# Callisto_LSOx10_v1p1.net
KiCad netlist of a schematic drawn in EAGLE
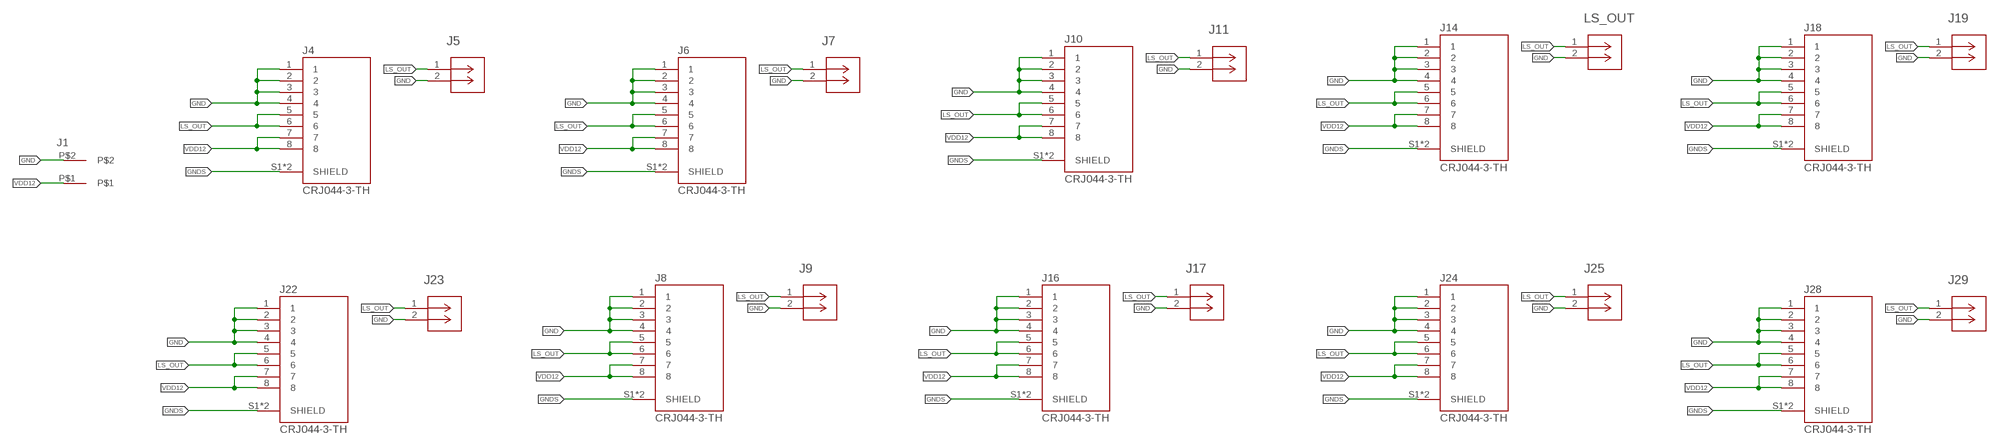
[diagram p0: schematic, sheet 1]

(export (version "E")
  (design (tool "Eeschema 10.0.6"))
  (components
    (comp (ref "J1")
      (value "2-pos")
      (footprint "eagle-import:2_3.81MM_PITCH")
      (fields (field (name "PARTNO") "691322310002"))
      (libsource (lib "eagle-import") (part "3.81MM_1_X_2_RT_ANGLE_PLUG_HEADER"))
    )
    (comp (ref "J4")
      (value "CRJ044-3-TH")
      (footprint "eagle-import:CUI_CRJ044-3-TH")
      (libsource (lib "eagle-import") (part "CRJ044-3-TH"))
    )
    (comp (ref "J5")
      (value "CONN_530470210_PICOBLADE_X_2")
      (footprint "eagle-import:CON_530470210_MOL")
      (fields
        (field (name "MANUFACTURER_PART_NUMBER") "530470210")
        (field (name "COPYRIGHT") "Copyright (C) 2022 Ultra Librarian. All rights reserved.")
      )
      (libsource (lib "eagle-import") (part "CONN_530470210_PICOBLADE_X_2"))
    )
    (comp (ref "J6")
      (value "CRJ044-3-TH")
      (footprint "eagle-import:CUI_CRJ044-3-TH")
      (libsource (lib "eagle-import") (part "CRJ044-3-TH"))
    )
    (comp (ref "J7")
      (value "CONN_530470210_PICOBLADE_X_2")
      (footprint "eagle-import:CON_530470210_MOL")
      (fields
        (field (name "MANUFACTURER_PART_NUMBER") "530470210")
        (field (name "COPYRIGHT") "Copyright (C) 2022 Ultra Librarian. All rights reserved.")
      )
      (libsource (lib "eagle-import") (part "CONN_530470210_PICOBLADE_X_2"))
    )
    (comp (ref "J8")
      (value "CRJ044-3-TH")
      (footprint "eagle-import:CUI_CRJ044-3-TH")
      (libsource (lib "eagle-import") (part "CRJ044-3-TH"))
    )
    (comp (ref "J9")
      (value "CONN_530470210_PICOBLADE_X_2")
      (footprint "eagle-import:CON_530470210_MOL")
      (fields
        (field (name "MANUFACTURER_PART_NUMBER") "530470210")
        (field (name "COPYRIGHT") "Copyright (C) 2022 Ultra Librarian. All rights reserved.")
      )
      (libsource (lib "eagle-import") (part "CONN_530470210_PICOBLADE_X_2"))
    )
    (comp (ref "J10")
      (value "CRJ044-3-TH")
      (footprint "eagle-import:CUI_CRJ044-3-TH")
      (libsource (lib "eagle-import") (part "CRJ044-3-TH"))
    )
    (comp (ref "J11")
      (value "CONN_530470210_PICOBLADE_X_2")
      (footprint "eagle-import:CON_530470210_MOL")
      (fields
        (field (name "MANUFACTURER_PART_NUMBER") "530470210")
        (field (name "COPYRIGHT") "Copyright (C) 2022 Ultra Librarian. All rights reserved.")
      )
      (libsource (lib "eagle-import") (part "CONN_530470210_PICOBLADE_X_2"))
    )
    (comp (ref "J14")
      (value "CRJ044-3-TH")
      (footprint "eagle-import:CUI_CRJ044-3-TH")
      (libsource (lib "eagle-import") (part "CRJ044-3-TH"))
    )
    (comp (ref "J16")
      (value "CRJ044-3-TH")
      (footprint "eagle-import:CUI_CRJ044-3-TH")
      (libsource (lib "eagle-import") (part "CRJ044-3-TH"))
    )
    (comp (ref "J17")
      (value "CONN_530470210_PICOBLADE_X_2")
      (footprint "eagle-import:CON_530470210_MOL")
      (fields
        (field (name "MANUFACTURER_PART_NUMBER") "530470210")
        (field (name "COPYRIGHT") "Copyright (C) 2022 Ultra Librarian. All rights reserved.")
      )
      (libsource (lib "eagle-import") (part "CONN_530470210_PICOBLADE_X_2"))
    )
    (comp (ref "J18")
      (value "CRJ044-3-TH")
      (footprint "eagle-import:CUI_CRJ044-3-TH")
      (libsource (lib "eagle-import") (part "CRJ044-3-TH"))
    )
    (comp (ref "J19")
      (value "CONN_530470210_PICOBLADE_X_2")
      (footprint "eagle-import:CON_530470210_MOL")
      (fields
        (field (name "MANUFACTURER_PART_NUMBER") "530470210")
        (field (name "COPYRIGHT") "Copyright (C) 2022 Ultra Librarian. All rights reserved.")
      )
      (libsource (lib "eagle-import") (part "CONN_530470210_PICOBLADE_X_2"))
    )
    (comp (ref "J22")
      (value "CRJ044-3-TH")
      (footprint "eagle-import:CUI_CRJ044-3-TH")
      (libsource (lib "eagle-import") (part "CRJ044-3-TH"))
    )
    (comp (ref "J23")
      (value "CONN_530470210_PICOBLADE_X_2")
      (footprint "eagle-import:CON_530470210_MOL")
      (fields
        (field (name "MANUFACTURER_PART_NUMBER") "530470210")
        (field (name "COPYRIGHT") "Copyright (C) 2022 Ultra Librarian. All rights reserved.")
      )
      (libsource (lib "eagle-import") (part "CONN_530470210_PICOBLADE_X_2"))
    )
    (comp (ref "J24")
      (value "CRJ044-3-TH")
      (footprint "eagle-import:CUI_CRJ044-3-TH")
      (libsource (lib "eagle-import") (part "CRJ044-3-TH"))
    )
    (comp (ref "J25")
      (value "CONN_530470210_PICOBLADE_X_2")
      (footprint "eagle-import:CON_530470210_MOL")
      (fields
        (field (name "MANUFACTURER_PART_NUMBER") "530470210")
        (field (name "COPYRIGHT") "Copyright (C) 2022 Ultra Librarian. All rights reserved.")
      )
      (libsource (lib "eagle-import") (part "CONN_530470210_PICOBLADE_X_2"))
    )
    (comp (ref "J28")
      (value "CRJ044-3-TH")
      (footprint "eagle-import:CUI_CRJ044-3-TH")
      (libsource (lib "eagle-import") (part "CRJ044-3-TH"))
    )
    (comp (ref "J29")
      (value "CONN_530470210_PICOBLADE_X_2")
      (footprint "eagle-import:CON_530470210_MOL")
      (fields
        (field (name "MANUFACTURER_PART_NUMBER") "530470210")
        (field (name "COPYRIGHT") "Copyright (C) 2022 Ultra Librarian. All rights reserved.")
      )
      (libsource (lib "eagle-import") (part "CONN_530470210_PICOBLADE_X_2"))
    )
    (comp (ref "LS_OUT")
      (value "CONN_530470210_PICOBLADE_X_2")
      (footprint "eagle-import:CON_530470210_MOL")
      (fields
        (field (name "MANUFACTURER_PART_NUMBER") "530470210")
        (field (name "COPYRIGHT") "Copyright (C) 2022 Ultra Librarian. All rights reserved.")
      )
      (libsource (lib "eagle-import") (part "CONN_530470210_PICOBLADE_X_2"))
    )
  )
  (nets
    (net (code "1") (name "GND") (class "Default")
      (node (ref "J1") (pin "P$2") (pinfunction "P$2_P$2") (pintype "bidirectional"))
      (node (ref "J10") (pin "1") (pinfunction "1_1") (pintype "passive"))
      (node (ref "J10") (pin "2") (pinfunction "2_2") (pintype "passive"))
      (node (ref "J10") (pin "3") (pinfunction "3_3") (pintype "passive"))
      (node (ref "J10") (pin "4") (pinfunction "4_4") (pintype "passive"))
      (node (ref "J11") (pin "2") (pinfunction "2_2") (pintype "passive"))
      (node (ref "J14") (pin "1") (pinfunction "1_1") (pintype "passive"))
      (node (ref "J14") (pin "2") (pinfunction "2_2") (pintype "passive"))
      (node (ref "J14") (pin "3") (pinfunction "3_3") (pintype "passive"))
      (node (ref "J14") (pin "4") (pinfunction "4_4") (pintype "passive"))
      (node (ref "J16") (pin "1") (pinfunction "1_1") (pintype "passive"))
      (node (ref "J16") (pin "2") (pinfunction "2_2") (pintype "passive"))
      (node (ref "J16") (pin "3") (pinfunction "3_3") (pintype "passive"))
      (node (ref "J16") (pin "4") (pinfunction "4_4") (pintype "passive"))
      (node (ref "J17") (pin "2") (pinfunction "2_2") (pintype "passive"))
      (node (ref "J18") (pin "1") (pinfunction "1_1") (pintype "passive"))
      (node (ref "J18") (pin "2") (pinfunction "2_2") (pintype "passive"))
      (node (ref "J18") (pin "3") (pinfunction "3_3") (pintype "passive"))
      (node (ref "J18") (pin "4") (pinfunction "4_4") (pintype "passive"))
      (node (ref "J19") (pin "2") (pinfunction "2_2") (pintype "passive"))
      (node (ref "J22") (pin "1") (pinfunction "1_1") (pintype "passive"))
      (node (ref "J22") (pin "2") (pinfunction "2_2") (pintype "passive"))
      (node (ref "J22") (pin "3") (pinfunction "3_3") (pintype "passive"))
      (node (ref "J22") (pin "4") (pinfunction "4_4") (pintype "passive"))
      (node (ref "J23") (pin "2") (pinfunction "2_2") (pintype "passive"))
      (node (ref "J24") (pin "1") (pinfunction "1_1") (pintype "passive"))
      (node (ref "J24") (pin "2") (pinfunction "2_2") (pintype "passive"))
      (node (ref "J24") (pin "3") (pinfunction "3_3") (pintype "passive"))
      (node (ref "J24") (pin "4") (pinfunction "4_4") (pintype "passive"))
      (node (ref "J25") (pin "2") (pinfunction "2_2") (pintype "passive"))
      (node (ref "J28") (pin "1") (pinfunction "1_1") (pintype "passive"))
      (node (ref "J28") (pin "2") (pinfunction "2_2") (pintype "passive"))
      (node (ref "J28") (pin "3") (pinfunction "3_3") (pintype "passive"))
      (node (ref "J28") (pin "4") (pinfunction "4_4") (pintype "passive"))
      (node (ref "J29") (pin "2") (pinfunction "2_2") (pintype "passive"))
      (node (ref "J4") (pin "1") (pinfunction "1_1") (pintype "passive"))
      (node (ref "J4") (pin "2") (pinfunction "2_2") (pintype "passive"))
      (node (ref "J4") (pin "3") (pinfunction "3_3") (pintype "passive"))
      (node (ref "J4") (pin "4") (pinfunction "4_4") (pintype "passive"))
      (node (ref "J5") (pin "2") (pinfunction "2_2") (pintype "passive"))
      (node (ref "J6") (pin "1") (pinfunction "1_1") (pintype "passive"))
      (node (ref "J6") (pin "2") (pinfunction "2_2") (pintype "passive"))
      (node (ref "J6") (pin "3") (pinfunction "3_3") (pintype "passive"))
      (node (ref "J6") (pin "4") (pinfunction "4_4") (pintype "passive"))
      (node (ref "J7") (pin "2") (pinfunction "2_2") (pintype "passive"))
      (node (ref "J8") (pin "1") (pinfunction "1_1") (pintype "passive"))
      (node (ref "J8") (pin "2") (pinfunction "2_2") (pintype "passive"))
      (node (ref "J8") (pin "3") (pinfunction "3_3") (pintype "passive"))
      (node (ref "J8") (pin "4") (pinfunction "4_4") (pintype "passive"))
      (node (ref "J9") (pin "2") (pinfunction "2_2") (pintype "passive"))
      (node (ref "LS_OUT") (pin "2") (pinfunction "2_2") (pintype "passive"))
    )
    (net (code "2") (name "GNDS") (class "Default")
      (node (ref "J10") (pin "S1") (pinfunction "SHIELD_S1") (pintype "passive"))
      (node (ref "J10") (pin "S2") (pinfunction "SHIELD_S2") (pintype "passive"))
      (node (ref "J14") (pin "S1") (pinfunction "SHIELD_S1") (pintype "passive"))
      (node (ref "J14") (pin "S2") (pinfunction "SHIELD_S2") (pintype "passive"))
      (node (ref "J16") (pin "S1") (pinfunction "SHIELD_S1") (pintype "passive"))
      (node (ref "J16") (pin "S2") (pinfunction "SHIELD_S2") (pintype "passive"))
      (node (ref "J18") (pin "S1") (pinfunction "SHIELD_S1") (pintype "passive"))
      (node (ref "J18") (pin "S2") (pinfunction "SHIELD_S2") (pintype "passive"))
      (node (ref "J22") (pin "S1") (pinfunction "SHIELD_S1") (pintype "passive"))
      (node (ref "J22") (pin "S2") (pinfunction "SHIELD_S2") (pintype "passive"))
      (node (ref "J24") (pin "S1") (pinfunction "SHIELD_S1") (pintype "passive"))
      (node (ref "J24") (pin "S2") (pinfunction "SHIELD_S2") (pintype "passive"))
      (node (ref "J28") (pin "S1") (pinfunction "SHIELD_S1") (pintype "passive"))
      (node (ref "J28") (pin "S2") (pinfunction "SHIELD_S2") (pintype "passive"))
      (node (ref "J4") (pin "S1") (pinfunction "SHIELD_S1") (pintype "passive"))
      (node (ref "J4") (pin "S2") (pinfunction "SHIELD_S2") (pintype "passive"))
      (node (ref "J6") (pin "S1") (pinfunction "SHIELD_S1") (pintype "passive"))
      (node (ref "J6") (pin "S2") (pinfunction "SHIELD_S2") (pintype "passive"))
      (node (ref "J8") (pin "S1") (pinfunction "SHIELD_S1") (pintype "passive"))
      (node (ref "J8") (pin "S2") (pinfunction "SHIELD_S2") (pintype "passive"))
    )
    (net (code "3") (name "LS_OUT") (class "Default")
      (node (ref "J10") (pin "5") (pinfunction "5_5") (pintype "passive"))
      (node (ref "J10") (pin "6") (pinfunction "6_6") (pintype "passive"))
      (node (ref "J11") (pin "1") (pinfunction "1_1") (pintype "passive"))
      (node (ref "J14") (pin "5") (pinfunction "5_5") (pintype "passive"))
      (node (ref "J14") (pin "6") (pinfunction "6_6") (pintype "passive"))
      (node (ref "J16") (pin "5") (pinfunction "5_5") (pintype "passive"))
      (node (ref "J16") (pin "6") (pinfunction "6_6") (pintype "passive"))
      (node (ref "J17") (pin "1") (pinfunction "1_1") (pintype "passive"))
      (node (ref "J18") (pin "5") (pinfunction "5_5") (pintype "passive"))
      (node (ref "J18") (pin "6") (pinfunction "6_6") (pintype "passive"))
      (node (ref "J19") (pin "1") (pinfunction "1_1") (pintype "passive"))
      (node (ref "J22") (pin "5") (pinfunction "5_5") (pintype "passive"))
      (node (ref "J22") (pin "6") (pinfunction "6_6") (pintype "passive"))
      (node (ref "J23") (pin "1") (pinfunction "1_1") (pintype "passive"))
      (node (ref "J24") (pin "5") (pinfunction "5_5") (pintype "passive"))
      (node (ref "J24") (pin "6") (pinfunction "6_6") (pintype "passive"))
      (node (ref "J25") (pin "1") (pinfunction "1_1") (pintype "passive"))
      (node (ref "J28") (pin "5") (pinfunction "5_5") (pintype "passive"))
      (node (ref "J28") (pin "6") (pinfunction "6_6") (pintype "passive"))
      (node (ref "J29") (pin "1") (pinfunction "1_1") (pintype "passive"))
      (node (ref "J4") (pin "5") (pinfunction "5_5") (pintype "passive"))
      (node (ref "J4") (pin "6") (pinfunction "6_6") (pintype "passive"))
      (node (ref "J5") (pin "1") (pinfunction "1_1") (pintype "passive"))
      (node (ref "J6") (pin "5") (pinfunction "5_5") (pintype "passive"))
      (node (ref "J6") (pin "6") (pinfunction "6_6") (pintype "passive"))
      (node (ref "J7") (pin "1") (pinfunction "1_1") (pintype "passive"))
      (node (ref "J8") (pin "5") (pinfunction "5_5") (pintype "passive"))
      (node (ref "J8") (pin "6") (pinfunction "6_6") (pintype "passive"))
      (node (ref "J9") (pin "1") (pinfunction "1_1") (pintype "passive"))
      (node (ref "LS_OUT") (pin "1") (pinfunction "1_1") (pintype "passive"))
    )
    (net (code "4") (name "VDD12") (class "Default")
      (node (ref "J1") (pin "P$1") (pinfunction "P$1_P$1") (pintype "bidirectional"))
      (node (ref "J10") (pin "7") (pinfunction "7_7") (pintype "passive"))
      (node (ref "J10") (pin "8") (pinfunction "8_8") (pintype "passive"))
      (node (ref "J14") (pin "7") (pinfunction "7_7") (pintype "passive"))
      (node (ref "J14") (pin "8") (pinfunction "8_8") (pintype "passive"))
      (node (ref "J16") (pin "7") (pinfunction "7_7") (pintype "passive"))
      (node (ref "J16") (pin "8") (pinfunction "8_8") (pintype "passive"))
      (node (ref "J18") (pin "7") (pinfunction "7_7") (pintype "passive"))
      (node (ref "J18") (pin "8") (pinfunction "8_8") (pintype "passive"))
      (node (ref "J22") (pin "7") (pinfunction "7_7") (pintype "passive"))
      (node (ref "J22") (pin "8") (pinfunction "8_8") (pintype "passive"))
      (node (ref "J24") (pin "7") (pinfunction "7_7") (pintype "passive"))
      (node (ref "J24") (pin "8") (pinfunction "8_8") (pintype "passive"))
      (node (ref "J28") (pin "7") (pinfunction "7_7") (pintype "passive"))
      (node (ref "J28") (pin "8") (pinfunction "8_8") (pintype "passive"))
      (node (ref "J4") (pin "7") (pinfunction "7_7") (pintype "passive"))
      (node (ref "J4") (pin "8") (pinfunction "8_8") (pintype "passive"))
      (node (ref "J6") (pin "7") (pinfunction "7_7") (pintype "passive"))
      (node (ref "J6") (pin "8") (pinfunction "8_8") (pintype "passive"))
      (node (ref "J8") (pin "7") (pinfunction "7_7") (pintype "passive"))
      (node (ref "J8") (pin "8") (pinfunction "8_8") (pintype "passive"))
    )
  )
)
